# 10scm153adp1_pwr.net
KiCad netlist of a schematic drawn in Altium Designer
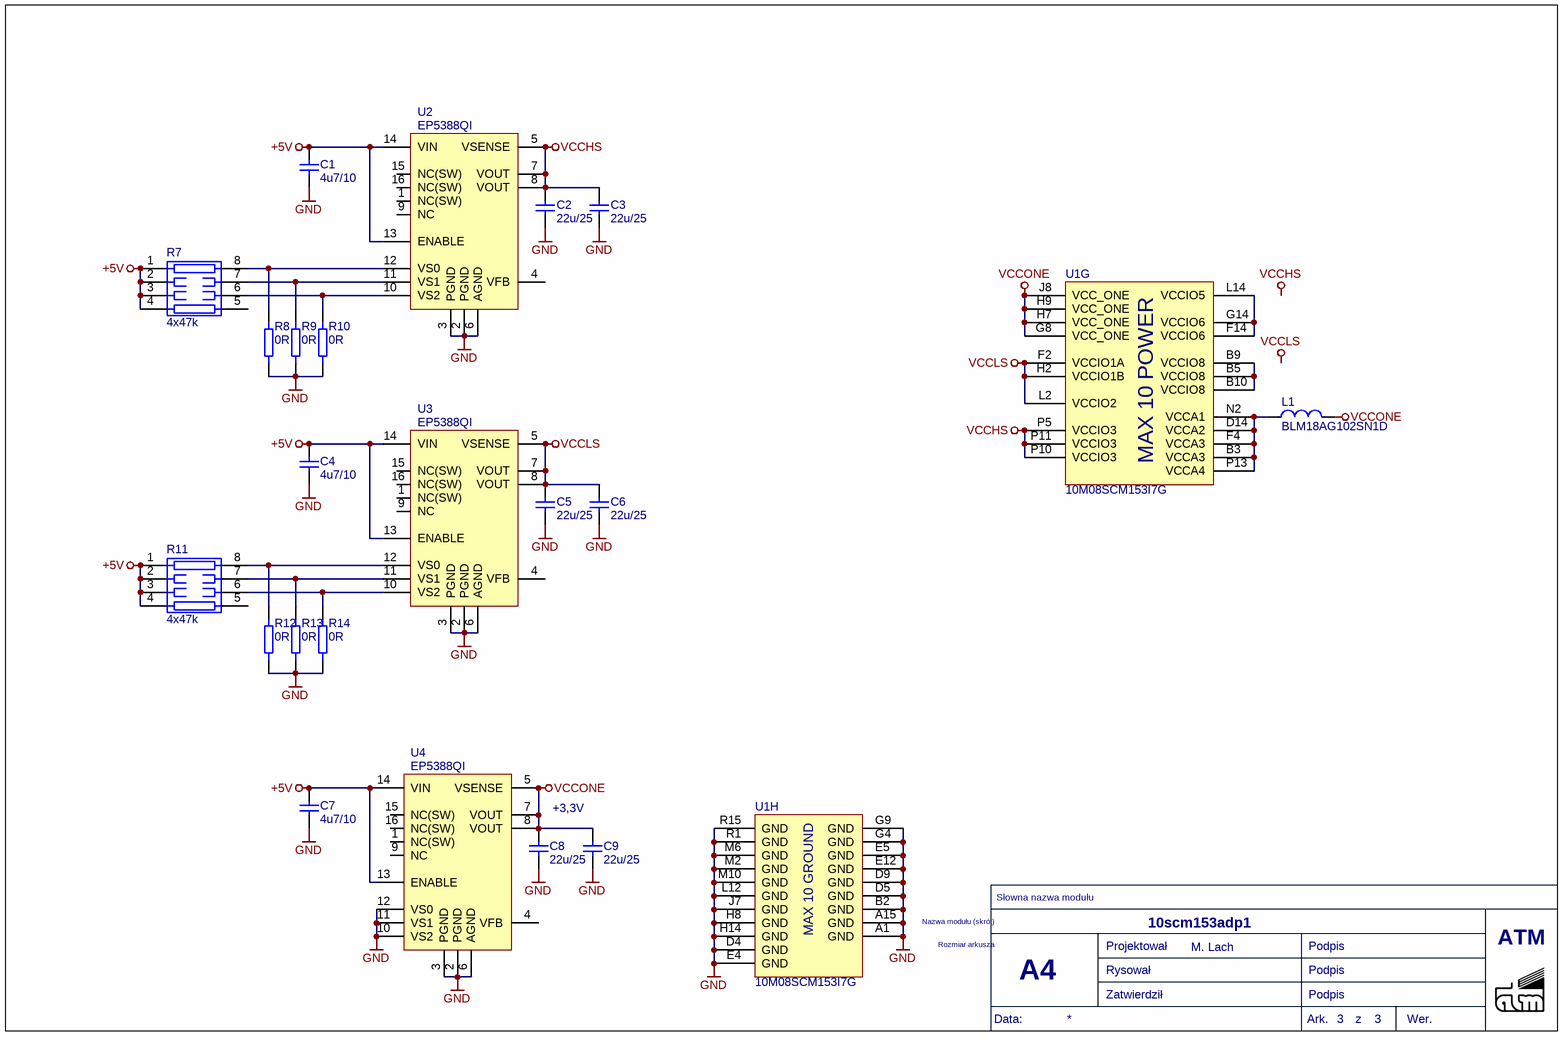
[diagram p0: 10scm153adp1_pwr.SchDoc]

(export (version "E")
  (design (tool "Eeschema 10.0.6"))
  (components
    (comp (ref "C1") (value "4u7/10") (footprint "0603-IPC") (libsource (lib "PartsMySQL") (part "C")))
    (comp (ref "C2") (value "22u/25") (footprint "0805") (libsource (lib "PartsMySQL") (part "C")))
    (comp (ref "C3") (value "22u/25") (footprint "0805") (libsource (lib "PartsMySQL") (part "C")))
    (comp (ref "C4") (value "4u7/10") (footprint "0603-IPC") (libsource (lib "PartsMySQL") (part "C")))
    (comp (ref "C5") (value "22u/25") (footprint "0805") (libsource (lib "PartsMySQL") (part "C")))
    (comp (ref "C6") (value "22u/25") (footprint "0805") (libsource (lib "PartsMySQL") (part "C")))
    (comp (ref "C7") (value "4u7/10") (footprint "0603-IPC") (libsource (lib "PartsMySQL") (part "C")))
    (comp (ref "C8") (value "22u/25") (footprint "0805") (libsource (lib "PartsMySQL") (part "C")))
    (comp (ref "C9") (value "22u/25") (footprint "0805") (libsource (lib "PartsMySQL") (part "C")))
    (comp (ref "L1")
      (value "BLM18AG102SN1D")
      (footprint "0603-IPC")
      (libsource (lib "PartsMySQL") (part "INDUCTOR"))
    )
    (comp (ref "R7") (value "4x47k") (footprint "1206RP") (libsource (lib "PartsMySQL") (part "DR1206")))
    (comp (ref "R8") (value "0R") (footprint "0603R") (libsource (lib "PartsMySQL") (part "R")))
    (comp (ref "R9") (value "0R") (footprint "0603R") (libsource (lib "PartsMySQL") (part "R")))
    (comp (ref "R10") (value "0R") (footprint "0603R") (libsource (lib "PartsMySQL") (part "R")))
    (comp (ref "R11") (value "4x47k") (footprint "1206RP") (libsource (lib "PartsMySQL") (part "DR1206")))
    (comp (ref "R12") (value "0R") (footprint "0603R") (libsource (lib "PartsMySQL") (part "R")))
    (comp (ref "R13") (value "0R") (footprint "0603R") (libsource (lib "PartsMySQL") (part "R")))
    (comp (ref "R14") (value "0R") (footprint "0603R") (libsource (lib "PartsMySQL") (part "R")))
    (comp (ref "U1")
      (value "10M08SCM153I7G")
      (footprint "MBGA153x15")
      (libsource (lib "PartsMySQL") (part "10M08SCM153"))
    )
    (comp (ref "U2")
      (value "EP5388QI")
      (footprint "EP5368QI")
      (libsource (lib "PartsMySQL") (part "EP5388QI"))
    )
    (comp (ref "U3")
      (value "EP5388QI")
      (footprint "EP5368QI")
      (libsource (lib "PartsMySQL") (part "EP5388QI"))
    )
    (comp (ref "U4")
      (value "EP5388QI")
      (footprint "EP5368QI")
      (libsource (lib "PartsMySQL") (part "EP5388QI"))
    )
  )
  (nets
    (net (code "1") (name "+5V") (class "Default")
      (node (ref "C1") (pin "1") (pinfunction "1_1") (pintype "passive"))
      (node (ref "C4") (pin "1") (pinfunction "1_1") (pintype "passive"))
      (node (ref "C7") (pin "1") (pinfunction "1_1") (pintype "passive"))
      (node (ref "R11") (pin "1") (pinfunction "R1_1") (pintype "passive"))
      (node (ref "R11") (pin "2") (pinfunction "R2_2") (pintype "passive"))
      (node (ref "R11") (pin "3") (pinfunction "R3_3") (pintype "passive"))
      (node (ref "R11") (pin "4") (pinfunction "R4_4") (pintype "passive"))
      (node (ref "R7") (pin "1") (pinfunction "R1_1") (pintype "passive"))
      (node (ref "R7") (pin "2") (pinfunction "R2_2") (pintype "passive"))
      (node (ref "R7") (pin "3") (pinfunction "R3_3") (pintype "passive"))
      (node (ref "R7") (pin "4") (pinfunction "R4_4") (pintype "passive"))
      (node (ref "U2") (pin "13") (pinfunction "ENABLE_13") (pintype "passive"))
      (node (ref "U2") (pin "14") (pinfunction "VIN_14") (pintype "passive"))
      (node (ref "U3") (pin "13") (pinfunction "ENABLE_13") (pintype "passive"))
      (node (ref "U3") (pin "14") (pinfunction "VIN_14") (pintype "passive"))
      (node (ref "U4") (pin "13") (pinfunction "ENABLE_13") (pintype "passive"))
      (node (ref "U4") (pin "14") (pinfunction "VIN_14") (pintype "passive"))
    )
    (net (code "2") (name "GND") (class "Default")
      (node (ref "C1") (pin "2") (pinfunction "2_2") (pintype "passive"))
      (node (ref "C2") (pin "2") (pinfunction "2_2") (pintype "passive"))
      (node (ref "C3") (pin "2") (pinfunction "2_2") (pintype "passive"))
      (node (ref "C4") (pin "2") (pinfunction "2_2") (pintype "passive"))
      (node (ref "C5") (pin "2") (pinfunction "2_2") (pintype "passive"))
      (node (ref "C6") (pin "2") (pinfunction "2_2") (pintype "passive"))
      (node (ref "C7") (pin "2") (pinfunction "2_2") (pintype "passive"))
      (node (ref "C8") (pin "2") (pinfunction "2_2") (pintype "passive"))
      (node (ref "C9") (pin "2") (pinfunction "2_2") (pintype "passive"))
      (node (ref "R10") (pin "2") (pinfunction "2_2") (pintype "passive"))
      (node (ref "R12") (pin "2") (pinfunction "2_2") (pintype "passive"))
      (node (ref "R13") (pin "2") (pinfunction "2_2") (pintype "passive"))
      (node (ref "R14") (pin "2") (pinfunction "2_2") (pintype "passive"))
      (node (ref "R8") (pin "2") (pinfunction "2_2") (pintype "passive"))
      (node (ref "R9") (pin "2") (pinfunction "2_2") (pintype "passive"))
      (node (ref "U1") (pin "A1") (pinfunction "GND_A1") (pintype "passive"))
      (node (ref "U1") (pin "A15") (pinfunction "GND_A15") (pintype "passive"))
      (node (ref "U1") (pin "B2") (pinfunction "GND_B2") (pintype "passive"))
      (node (ref "U1") (pin "D4") (pinfunction "GND_D4") (pintype "passive"))
      (node (ref "U1") (pin "D5") (pinfunction "GND_D5") (pintype "passive"))
      (node (ref "U1") (pin "D9") (pinfunction "GND_D9") (pintype "passive"))
      (node (ref "U1") (pin "E12") (pinfunction "GND_E12") (pintype "passive"))
      (node (ref "U1") (pin "E4") (pinfunction "GND_E4") (pintype "passive"))
      (node (ref "U1") (pin "E5") (pinfunction "GND_E5") (pintype "passive"))
      (node (ref "U1") (pin "G4") (pinfunction "GND_G4") (pintype "passive"))
      (node (ref "U1") (pin "G9") (pinfunction "GND_G9") (pintype "passive"))
      (node (ref "U1") (pin "H14") (pinfunction "GND_H14") (pintype "passive"))
      (node (ref "U1") (pin "H8") (pinfunction "GND_H8") (pintype "passive"))
      (node (ref "U1") (pin "J7") (pinfunction "GND_J7") (pintype "passive"))
      (node (ref "U1") (pin "L12") (pinfunction "GND_L12") (pintype "passive"))
      (node (ref "U1") (pin "M10") (pinfunction "GND_M10") (pintype "passive"))
      (node (ref "U1") (pin "M2") (pinfunction "GND_M2") (pintype "passive"))
      (node (ref "U1") (pin "M6") (pinfunction "GND_M6") (pintype "passive"))
      (node (ref "U1") (pin "R1") (pinfunction "GND_R1") (pintype "passive"))
      (node (ref "U1") (pin "R15") (pinfunction "GND_R15") (pintype "passive"))
      (node (ref "U2") (pin "2") (pinfunction "PGND_2") (pintype "passive"))
      (node (ref "U2") (pin "3") (pinfunction "PGND_3") (pintype "passive"))
      (node (ref "U2") (pin "6") (pinfunction "AGND_6") (pintype "passive"))
      (node (ref "U3") (pin "2") (pinfunction "PGND_2") (pintype "passive"))
      (node (ref "U3") (pin "3") (pinfunction "PGND_3") (pintype "passive"))
      (node (ref "U3") (pin "6") (pinfunction "AGND_6") (pintype "passive"))
      (node (ref "U4") (pin "10") (pinfunction "VS2_10") (pintype "passive"))
      (node (ref "U4") (pin "11") (pinfunction "VS1_11") (pintype "passive"))
      (node (ref "U4") (pin "12") (pinfunction "VS0_12") (pintype "passive"))
      (node (ref "U4") (pin "2") (pinfunction "PGND_2") (pintype "passive"))
      (node (ref "U4") (pin "3") (pinfunction "PGND_3") (pintype "passive"))
      (node (ref "U4") (pin "6") (pinfunction "AGND_6") (pintype "passive"))
    )
    (net (code "3") (name "Net-(R7-R6)") (class "Default")
      (node (ref "R10") (pin "1") (pinfunction "1_1") (pintype "passive"))
      (node (ref "R7") (pin "6") (pinfunction "R6_6") (pintype "passive"))
      (node (ref "U2") (pin "10") (pinfunction "VS2_10") (pintype "passive"))
    )
    (net (code "4") (name "Net-(R7-R7)") (class "Default")
      (node (ref "R7") (pin "7") (pinfunction "R7_7") (pintype "passive"))
      (node (ref "R9") (pin "1") (pinfunction "1_1") (pintype "passive"))
      (node (ref "U2") (pin "11") (pinfunction "VS1_11") (pintype "passive"))
    )
    (net (code "5") (name "Net-(R7-R8)") (class "Default")
      (node (ref "R7") (pin "8") (pinfunction "R8_8") (pintype "passive"))
      (node (ref "R8") (pin "1") (pinfunction "1_1") (pintype "passive"))
      (node (ref "U2") (pin "12") (pinfunction "VS0_12") (pintype "passive"))
    )
    (net (code "6") (name "Net-(R11-R6)") (class "Default")
      (node (ref "R11") (pin "6") (pinfunction "R6_6") (pintype "passive"))
      (node (ref "R14") (pin "1") (pinfunction "1_1") (pintype "passive"))
      (node (ref "U3") (pin "10") (pinfunction "VS2_10") (pintype "passive"))
    )
    (net (code "7") (name "Net-(R11-R7)") (class "Default")
      (node (ref "R11") (pin "7") (pinfunction "R7_7") (pintype "passive"))
      (node (ref "R13") (pin "1") (pinfunction "1_1") (pintype "passive"))
      (node (ref "U3") (pin "11") (pinfunction "VS1_11") (pintype "passive"))
    )
    (net (code "8") (name "Net-(R11-R8)") (class "Default")
      (node (ref "R11") (pin "8") (pinfunction "R8_8") (pintype "passive"))
      (node (ref "R12") (pin "1") (pinfunction "1_1") (pintype "passive"))
      (node (ref "U3") (pin "12") (pinfunction "VS0_12") (pintype "passive"))
    )
    (net (code "9") (name "Net-(U1G-VCCA1)") (class "Default")
      (node (ref "L1") (pin "1") (pinfunction "1_1") (pintype "passive"))
      (node (ref "U1") (pin "B3") (pinfunction "VCCA3_B3") (pintype "passive"))
      (node (ref "U1") (pin "D14") (pinfunction "VCCA2_D14") (pintype "passive"))
      (node (ref "U1") (pin "F4") (pinfunction "VCCA3_F4") (pintype "passive"))
      (node (ref "U1") (pin "N2") (pinfunction "VCCA1_N2") (pintype "passive"))
      (node (ref "U1") (pin "P13") (pinfunction "VCCA4_P13") (pintype "passive"))
    )
    (net (code "10") (name "Net-(U1G-VCCIO5)") (class "Default")
      (node (ref "U1") (pin "F14") (pinfunction "VCCIO6_F14") (pintype "passive"))
      (node (ref "U1") (pin "G14") (pinfunction "VCCIO6_G14") (pintype "passive"))
      (node (ref "U1") (pin "L14") (pinfunction "VCCIO5_L14") (pintype "passive"))
    )
    (net (code "11") (name "Net-(U1G-VCCIO8-PadB10)") (class "Default")
      (node (ref "U1") (pin "B10") (pinfunction "VCCIO8_B10") (pintype "passive"))
      (node (ref "U1") (pin "B5") (pinfunction "VCCIO8_B5") (pintype "passive"))
      (node (ref "U1") (pin "B9") (pinfunction "VCCIO8_B9") (pintype "passive"))
    )
    (net (code "12") (name "VCCHS") (class "Default")
      (node (ref "C2") (pin "1") (pinfunction "1_1") (pintype "passive"))
      (node (ref "C3") (pin "1") (pinfunction "1_1") (pintype "passive"))
      (node (ref "U1") (pin "P10") (pinfunction "VCCIO3_P10") (pintype "passive"))
      (node (ref "U1") (pin "P11") (pinfunction "VCCIO3_P11") (pintype "passive"))
      (node (ref "U1") (pin "P5") (pinfunction "VCCIO3_P5") (pintype "passive"))
      (node (ref "U2") (pin "5") (pinfunction "VSENSE_5") (pintype "passive"))
      (node (ref "U2") (pin "7") (pinfunction "VOUT_7") (pintype "passive"))
      (node (ref "U2") (pin "8") (pinfunction "VOUT_8") (pintype "passive"))
    )
    (net (code "13") (name "VCCLS") (class "Default")
      (node (ref "C5") (pin "1") (pinfunction "1_1") (pintype "passive"))
      (node (ref "C6") (pin "1") (pinfunction "1_1") (pintype "passive"))
      (node (ref "U1") (pin "F2") (pinfunction "VCCIO1A_F2") (pintype "passive"))
      (node (ref "U1") (pin "H2") (pinfunction "VCCIO1B_H2") (pintype "passive"))
      (node (ref "U1") (pin "L2") (pinfunction "VCCIO2_L2") (pintype "passive"))
      (node (ref "U3") (pin "5") (pinfunction "VSENSE_5") (pintype "passive"))
      (node (ref "U3") (pin "7") (pinfunction "VOUT_7") (pintype "passive"))
      (node (ref "U3") (pin "8") (pinfunction "VOUT_8") (pintype "passive"))
    )
    (net (code "14") (name "VCCONE") (class "Default")
      (node (ref "C8") (pin "1") (pinfunction "1_1") (pintype "passive"))
      (node (ref "C9") (pin "1") (pinfunction "1_1") (pintype "passive"))
      (node (ref "L1") (pin "2") (pinfunction "2_2") (pintype "passive"))
      (node (ref "U1") (pin "G8") (pinfunction "VCC_ONE_G8") (pintype "passive"))
      (node (ref "U1") (pin "H7") (pinfunction "VCC_ONE_H7") (pintype "passive"))
      (node (ref "U1") (pin "H9") (pinfunction "VCC_ONE_H9") (pintype "passive"))
      (node (ref "U1") (pin "J8") (pinfunction "VCC_ONE_J8") (pintype "passive"))
      (node (ref "U4") (pin "5") (pinfunction "VSENSE_5") (pintype "passive"))
      (node (ref "U4") (pin "7") (pinfunction "VOUT_7") (pintype "passive"))
      (node (ref "U4") (pin "8") (pinfunction "VOUT_8") (pintype "passive"))
    )
    (net (code "15") (name "unconnected-(R7-R5-Pad5)") (class "Default")
      (node (ref "R7") (pin "5") (pinfunction "R5_5") (pintype "passive"))
    )
    (net (code "16") (name "unconnected-(R11-R5-Pad5)") (class "Default")
      (node (ref "R11") (pin "5") (pinfunction "R5_5") (pintype "passive"))
    )
    (net (code "17") (name "unconnected-(U2-NC(SW)-Pad1)") (class "Default")
      (node (ref "U2") (pin "1") (pinfunction "NC(SW)_1") (pintype "passive"))
    )
    (net (code "18") (name "unconnected-(U2-NC(SW)-Pad15)") (class "Default")
      (node (ref "U2") (pin "15") (pinfunction "NC(SW)_15") (pintype "passive"))
    )
    (net (code "19") (name "unconnected-(U2-NC(SW)-Pad16)") (class "Default")
      (node (ref "U2") (pin "16") (pinfunction "NC(SW)_16") (pintype "passive"))
    )
    (net (code "20") (name "unconnected-(U2-NC-Pad9)") (class "Default")
      (node (ref "U2") (pin "9") (pinfunction "NC_9") (pintype "passive"))
    )
    (net (code "21") (name "unconnected-(U2-VFB-Pad4)") (class "Default")
      (node (ref "U2") (pin "4") (pinfunction "VFB_4") (pintype "passive"))
    )
    (net (code "22") (name "unconnected-(U3-NC(SW)-Pad1)") (class "Default")
      (node (ref "U3") (pin "1") (pinfunction "NC(SW)_1") (pintype "passive"))
    )
    (net (code "23") (name "unconnected-(U3-NC(SW)-Pad15)") (class "Default")
      (node (ref "U3") (pin "15") (pinfunction "NC(SW)_15") (pintype "passive"))
    )
    (net (code "24") (name "unconnected-(U3-NC(SW)-Pad16)") (class "Default")
      (node (ref "U3") (pin "16") (pinfunction "NC(SW)_16") (pintype "passive"))
    )
    (net (code "25") (name "unconnected-(U3-NC-Pad9)") (class "Default")
      (node (ref "U3") (pin "9") (pinfunction "NC_9") (pintype "passive"))
    )
    (net (code "26") (name "unconnected-(U3-VFB-Pad4)") (class "Default")
      (node (ref "U3") (pin "4") (pinfunction "VFB_4") (pintype "passive"))
    )
    (net (code "27") (name "unconnected-(U4-NC(SW)-Pad1)") (class "Default")
      (node (ref "U4") (pin "1") (pinfunction "NC(SW)_1") (pintype "passive"))
    )
    (net (code "28") (name "unconnected-(U4-NC(SW)-Pad15)") (class "Default")
      (node (ref "U4") (pin "15") (pinfunction "NC(SW)_15") (pintype "passive"))
    )
    (net (code "29") (name "unconnected-(U4-NC(SW)-Pad16)") (class "Default")
      (node (ref "U4") (pin "16") (pinfunction "NC(SW)_16") (pintype "passive"))
    )
    (net (code "30") (name "unconnected-(U4-NC-Pad9)") (class "Default")
      (node (ref "U4") (pin "9") (pinfunction "NC_9") (pintype "passive"))
    )
    (net (code "31") (name "unconnected-(U4-VFB-Pad4)") (class "Default")
      (node (ref "U4") (pin "4") (pinfunction "VFB_4") (pintype "passive"))
    )
  )
)
